# SCH_Ducky.net
KiCad netlist of a schematic drawn in EasyEDA
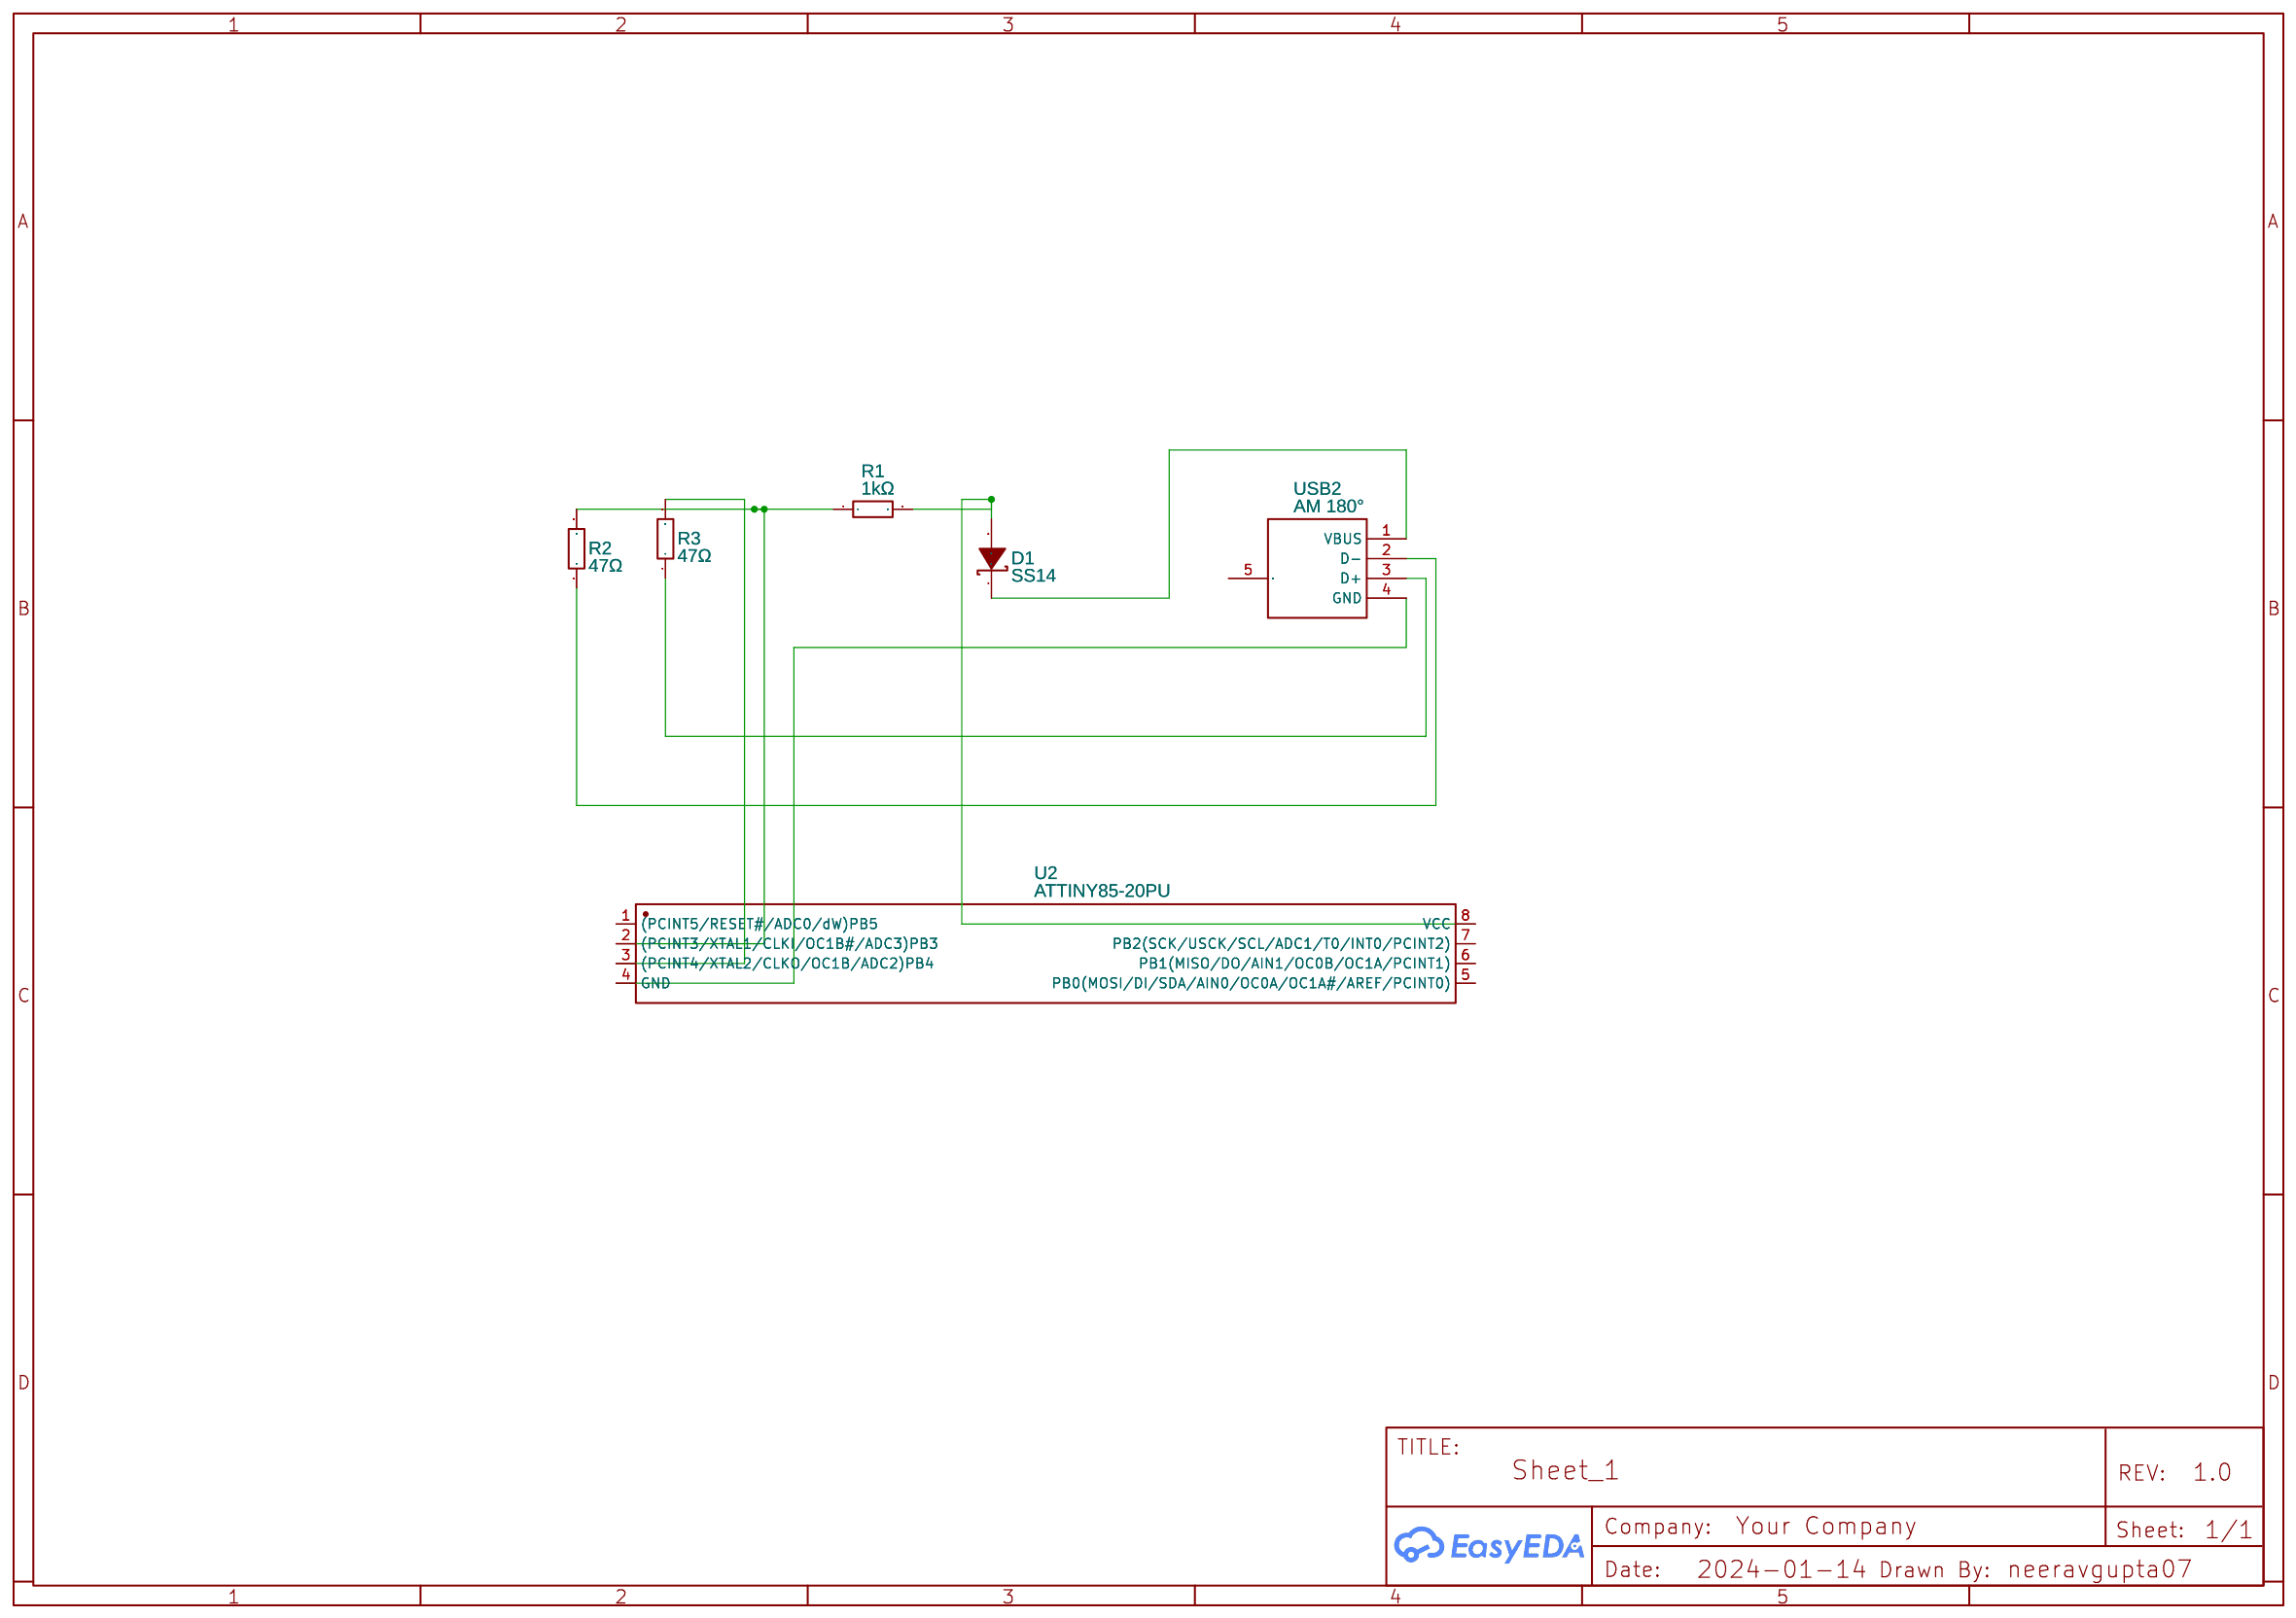
[diagram p0: schematic sheet]

(export (version "E")
  (design (tool "Eeschema 10.0.6"))
  (components
    (comp (ref "D1")
      (value "SS14")
      (fields (field (name "Manufacturer") "MDD"))
      (libsource (lib "") (part "SS14"))
    )
    (comp (ref "R1")
      (value "1kΩ")
      (fields
        (field (name "Manufacturer Part") "0603WAF1001T5E")
        (field (name "Manufacturer") "UNI-ROYAL(厚声)")
      )
      (libsource (lib "") (part "0603WAF1001T5E"))
    )
    (comp (ref "R2")
      (value "47Ω")
      (fields
        (field (name "Manufacturer Part") "0603WAF470JT5E")
        (field (name "Manufacturer") "UNI-ROYAL(厚声)")
      )
      (libsource (lib "") (part "0603WAF470JT5E"))
    )
    (comp (ref "R3")
      (value "47Ω")
      (fields
        (field (name "Manufacturer Part") "0603WAF470JT5E")
        (field (name "Manufacturer") "UNI-ROYAL(厚声)")
      )
      (libsource (lib "") (part "0603WAF470JT5E"))
    )
    (comp (ref "U2")
      (value "ATTINY85-20PU")
      (fields (field (name "Manufacturer") "MICROCHIP(美国微芯)"))
      (libsource (lib "") (part "ATTINY85-20PU"))
    )
    (comp (ref "USB2")
      (value "AM 180°")
      (fields (field (name "Manufacturer") "SHOU HAN(首韩)"))
      (libsource (lib "") (part "AM 180°"))
    )
  )
  (nets
    (net (code "1") (name "Net-(D1-A)") (class "Default")
      (node (ref "D1") (pin "2") (pinfunction "A_2") (pintype "unspecified"))
      (node (ref "R1") (pin "2") (pinfunction "2_2") (pintype "input"))
      (node (ref "U2") (pin "8") (pinfunction "VCC_8") (pintype "unspecified"))
    )
    (net (code "2") (name "Net-(D1-K)") (class "Default")
      (node (ref "D1") (pin "1") (pinfunction "K_1") (pintype "unspecified"))
      (node (ref "USB2") (pin "1") (pinfunction "VBUS_1") (pintype "input"))
    )
    (net (code "3") (name "Net-(U2-(PCINT3{slash}XTAL1{slash}CLKI{slash}OC1B#{slash}ADC3)PB3)") (class "Default")
      (node (ref "R1") (pin "1") (pinfunction "1_1") (pintype "input"))
      (node (ref "R2") (pin "2") (pinfunction "2_2") (pintype "input"))
      (node (ref "U2") (pin "2") (pinfunction "(PCINT3/XTAL1/CLKI/OC1B#/ADC3)PB3_2") (pintype "unspecified"))
    )
    (net (code "4") (name "Net-(U2-(PCINT4{slash}XTAL2{slash}CLKO{slash}OC1B{slash}ADC2)PB4)") (class "Default")
      (node (ref "R3") (pin "2") (pinfunction "2_2") (pintype "input"))
      (node (ref "U2") (pin "3") (pinfunction "(PCINT4/XTAL2/CLKO/OC1B/ADC2)PB4_3") (pintype "unspecified"))
    )
    (net (code "5") (name "Net-(U2-GND)") (class "Default")
      (node (ref "U2") (pin "4") (pinfunction "GND_4") (pintype "unspecified"))
      (node (ref "USB2") (pin "4") (pinfunction "GND_4") (pintype "input"))
    )
    (net (code "6") (name "Net-(USB2-D+)") (class "Default")
      (node (ref "R3") (pin "1") (pinfunction "1_1") (pintype "input"))
      (node (ref "USB2") (pin "3") (pinfunction "D+_3") (pintype "input"))
    )
    (net (code "7") (name "Net-(USB2-D-)") (class "Default")
      (node (ref "R2") (pin "1") (pinfunction "1_1") (pintype "input"))
      (node (ref "USB2") (pin "2") (pinfunction "D-_2") (pintype "input"))
    )
    (net (code "8") (name "unconnected-(U2-(PCINT5{slash}RESET#{slash}ADC0{slash}dW)PB5-Pad1)") (class "Default")
      (node (ref "U2") (pin "1") (pinfunction "(PCINT5/RESET#/ADC0/dW)PB5_1") (pintype "unspecified"))
    )
    (net (code "9") (name "unconnected-(U2-PB0(MOSI{slash}DI{slash}SDA{slash}AIN0{slash}OC0A{slash}OC1A#{slash}AREF{slash}PCINT0)-Pad5)") (class "Default")
      (node (ref "U2") (pin "5") (pinfunction "PB0(MOSI/DI/SDA/AIN0/OC0A/OC1A#/AREF/PCINT0)_5") (pintype "unspecified"))
    )
    (net (code "10") (name "unconnected-(U2-PB1(MISO{slash}DO{slash}AIN1{slash}OC0B{slash}OC1A{slash}PCINT1)-Pad6)") (class "Default")
      (node (ref "U2") (pin "6") (pinfunction "PB1(MISO/DO/AIN1/OC0B/OC1A/PCINT1)_6") (pintype "unspecified"))
    )
    (net (code "11") (name "unconnected-(U2-PB2(SCK{slash}USCK{slash}SCL{slash}ADC1{slash}T0{slash}INT0{slash}PCINT2)-Pad7)") (class "Default")
      (node (ref "U2") (pin "7") (pinfunction "PB2(SCK/USCK/SCL/ADC1/T0/INT0/PCINT2)_7") (pintype "unspecified"))
    )
    (net (code "12") (name "unconnected-(USB2-EH-Pad5)") (class "Default")
      (node (ref "USB2") (pin "5") (pinfunction "EH_5") (pintype "input"))
    )
  )
)
